# MCU.net
KiCad netlist of a schematic drawn in Altium Designer
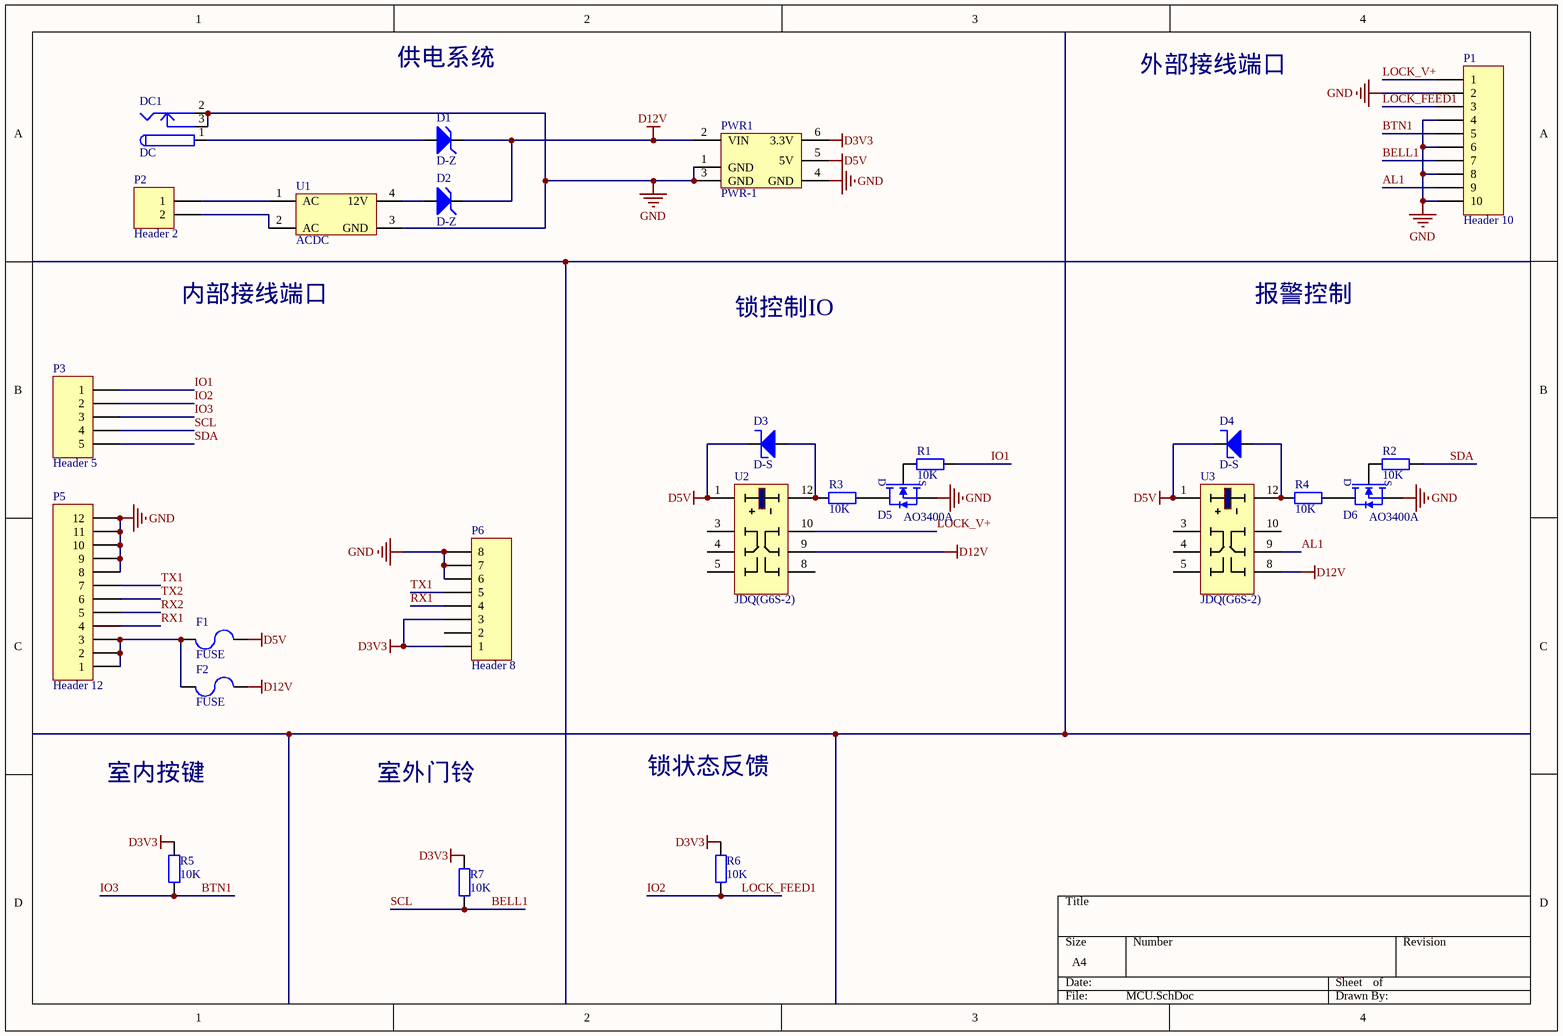
[diagram p0: MCU.SchDoc]

(export (version "E")
  (design (tool "Eeschema 10.0.6"))
  (components
    (comp (ref "D1")
      (value "D-Z")
      (footprint "DO-214AC(SMA)")
      (description "稳压二极管")
      (libsource (lib "lib_AD") (part "D-Z"))
    )
    (comp (ref "D2")
      (value "D-Z")
      (footprint "DO-214AC(SMA)")
      (description "稳压二极管")
      (libsource (lib "lib_AD") (part "D-Z"))
    )
    (comp (ref "D3")
      (value "D-S")
      (footprint "DO-214AC(SMA)")
      (description "肖特基二极管")
      (libsource (lib "lib_AD") (part "D-S"))
    )
    (comp (ref "D4")
      (value "D-S")
      (footprint "DO-214AC(SMA)")
      (description "肖特基二极管")
      (libsource (lib "lib_AD") (part "D-S"))
    )
    (comp (ref "D5")
      (value "AO3400A")
      (footprint "SOT23A")
      (description "NMOS")
      (libsource (lib "lib_AD") (part "MOS-N"))
    )
    (comp (ref "D6")
      (value "AO3400A")
      (footprint "SOT23A")
      (description "NMOS")
      (libsource (lib "lib_AD") (part "MOS-N"))
    )
    (comp (ref "DC1")
      (value "DC")
      (footprint "DC005")
      (description "圆形电源接口")
      (libsource (lib "lib_AD") (part "DC00X"))
    )
    (comp (ref "F1")
      (value "FUSE")
      (footprint "0805F")
      (description "CR-1812-050A60V")
      (libsource (lib "lib_AD") (part "FUSE"))
    )
    (comp (ref "F2")
      (value "FUSE")
      (footprint "0805F")
      (description "CR-1812-050A60V")
      (libsource (lib "lib_AD") (part "FUSE"))
    )
    (comp (ref "P1")
      (value "Header 10")
      (footprint "KF128-5.08-10")
      (description "Header, 10-Pin")
      (fields (field (name "PUBLISHER") "Altium Limited"))
      (libsource (lib "lib_AD") (part "Header 10"))
    )
    (comp (ref "P2")
      (value "Header 2")
      (footprint "KF128-5.08-2")
      (description "Header, 2-Pin")
      (fields (field (name "PUBLISHER") "Altium Limited"))
      (libsource (lib "lib_AD") (part "Header 2"))
    )
    (comp (ref "P3")
      (value "Header 5")
      (footprint "XH2.54-5")
      (description "Header, 5-Pin")
      (fields (field (name "PUBLISHER") "Altium Limited"))
      (libsource (lib "lib_AD") (part "Header 5"))
    )
    (comp (ref "P5")
      (value "Header 12")
      (footprint "FFC/SM1.0-2H10")
      (description "Header, 12-Pin")
      (fields (field (name "PUBLISHER") "Altium Limited"))
      (libsource (lib "lib_AD") (part "Header 12"))
    )
    (comp (ref "P6")
      (value "Header 8")
      (footprint "FPC/1.25T-6P")
      (description "Header, 8-Pin")
      (fields (field (name "PUBLISHER") "Altium Limited"))
      (libsource (lib "lib_AD") (part "Header 8"))
    )
    (comp (ref "PWR1") (value "PWR-1") (footprint "PWR-1") (libsource (lib "lib_AD") (part "PWR-1")))
    (comp (ref "R1")
      (value "10K")
      (footprint "0603R")
      (description "普通电阻")
      (libsource (lib "") (part "RES_1"))
    )
    (comp (ref "R2")
      (value "10K")
      (footprint "0603R")
      (description "普通电阻")
      (libsource (lib "") (part "RES_1"))
    )
    (comp (ref "R3")
      (value "10K")
      (footprint "0603R")
      (description "普通电阻")
      (libsource (lib "") (part "RES_1"))
    )
    (comp (ref "R4")
      (value "10K")
      (footprint "0603R")
      (description "普通电阻")
      (libsource (lib "") (part "RES_1"))
    )
    (comp (ref "R5")
      (value "10K")
      (footprint "0603R")
      (description "普通电阻")
      (libsource (lib "lib_AD") (part "RES"))
    )
    (comp (ref "R6")
      (value "10K")
      (footprint "0603R")
      (description "普通电阻")
      (libsource (lib "lib_AD") (part "RES"))
    )
    (comp (ref "R7")
      (value "10K")
      (footprint "0603R")
      (description "普通电阻")
      (libsource (lib "lib_AD") (part "RES"))
    )
    (comp (ref "U1") (value "ACDC") (footprint "ACDC") (libsource (lib "Misc") (part "ACDC12")))
    (comp (ref "U2")
      (value "JDQ(G6S-2)")
      (footprint "JDQ-G6S-2")
      (description "继电器（G6S-2 5VDC）")
      (libsource (lib "lib_AD") (part "JDQ(G6S-2)"))
    )
    (comp (ref "U3")
      (value "JDQ(G6S-2)")
      (footprint "JDQ-G6S-2")
      (description "继电器（G6S-2 5VDC）")
      (libsource (lib "lib_AD") (part "JDQ(G6S-2)"))
    )
  )
  (nets
    (net (code "1") (name "/AL1") (class "Default")
      (node (ref "P1") (pin "9") (pinfunction "9_9") (pintype "passive"))
      (node (ref "U3") (pin "9") (pinfunction "9_9") (pintype "passive"))
    )
    (net (code "2") (name "/BELL1") (class "Default")
      (node (ref "P1") (pin "7") (pinfunction "7_7") (pintype "passive"))
      (node (ref "P3") (pin "4") (pinfunction "4_4") (pintype "passive"))
      (node (ref "R7") (pin "1") (pinfunction "1_1") (pintype "passive"))
    )
    (net (code "3") (name "/BTN1") (class "Default")
      (node (ref "P1") (pin "5") (pinfunction "5_5") (pintype "passive"))
      (node (ref "P3") (pin "3") (pinfunction "3_3") (pintype "passive"))
      (node (ref "R5") (pin "1") (pinfunction "1_1") (pintype "passive"))
    )
    (net (code "4") (name "/IO1") (class "Default")
      (node (ref "P3") (pin "1") (pinfunction "1_1") (pintype "passive"))
      (node (ref "R1") (pin "2") (pinfunction "2_2") (pintype "passive"))
    )
    (net (code "5") (name "/IO2") (class "Default")
      (node (ref "P1") (pin "3") (pinfunction "3_3") (pintype "passive"))
      (node (ref "P3") (pin "2") (pinfunction "2_2") (pintype "passive"))
      (node (ref "R6") (pin "1") (pinfunction "1_1") (pintype "passive"))
    )
    (net (code "6") (name "/LOCK_V+") (class "Default")
      (node (ref "P1") (pin "1") (pinfunction "1_1") (pintype "passive"))
      (node (ref "U2") (pin "10") (pinfunction "10_10") (pintype "passive"))
    )
    (net (code "7") (name "/RX1") (class "Default")
      (node (ref "P5") (pin "4") (pinfunction "4_4") (pintype "passive"))
      (node (ref "P6") (pin "4") (pinfunction "4_4") (pintype "passive"))
    )
    (net (code "8") (name "/RX2") (class "Default")
      (node (ref "P5") (pin "5") (pinfunction "5_5") (pintype "passive"))
    )
    (net (code "9") (name "/SDA") (class "Default")
      (node (ref "P3") (pin "5") (pinfunction "5_5") (pintype "passive"))
      (node (ref "R2") (pin "2") (pinfunction "2_2") (pintype "passive"))
    )
    (net (code "10") (name "/TX1") (class "Default")
      (node (ref "P5") (pin "7") (pinfunction "7_7") (pintype "passive"))
      (node (ref "P6") (pin "5") (pinfunction "5_5") (pintype "passive"))
    )
    (net (code "11") (name "/TX2") (class "Default")
      (node (ref "P5") (pin "6") (pinfunction "6_6") (pintype "passive"))
    )
    (net (code "12") (name "D3V3") (class "Default")
      (node (ref "P6") (pin "1") (pinfunction "1_1") (pintype "passive"))
      (node (ref "P6") (pin "3") (pinfunction "3_3") (pintype "passive"))
      (node (ref "PWR1") (pin "6") (pinfunction "3.3V_6") (pintype "passive"))
      (node (ref "R5") (pin "2") (pinfunction "2_2") (pintype "passive"))
      (node (ref "R6") (pin "2") (pinfunction "2_2") (pintype "passive"))
      (node (ref "R7") (pin "2") (pinfunction "2_2") (pintype "passive"))
    )
    (net (code "13") (name "D5V") (class "Default")
      (node (ref "D3") (pin "K") (pinfunction "2_K") (pintype "passive"))
      (node (ref "D4") (pin "K") (pinfunction "2_K") (pintype "passive"))
      (node (ref "F1") (pin "1") (pinfunction "1_1") (pintype "passive"))
      (node (ref "PWR1") (pin "5") (pinfunction "5V_5") (pintype "passive"))
      (node (ref "U2") (pin "1") (pinfunction "1_1") (pintype "passive"))
      (node (ref "U3") (pin "1") (pinfunction "1_1") (pintype "passive"))
    )
    (net (code "14") (name "D12V") (class "Default")
      (node (ref "D1") (pin "K") (pinfunction "2_K") (pintype "passive"))
      (node (ref "D2") (pin "K") (pinfunction "2_K") (pintype "passive"))
      (node (ref "F2") (pin "1") (pinfunction "1_1") (pintype "passive"))
      (node (ref "PWR1") (pin "2") (pinfunction "VIN_2") (pintype "passive"))
      (node (ref "U2") (pin "9") (pinfunction "9_9") (pintype "passive"))
      (node (ref "U3") (pin "8") (pinfunction "8_8") (pintype "passive"))
    )
    (net (code "15") (name "GND") (class "Default")
      (node (ref "D5") (pin "2") (pinfunction "S_2") (pintype "passive"))
      (node (ref "D6") (pin "2") (pinfunction "S_2") (pintype "passive"))
      (node (ref "DC1") (pin "2") (pinfunction "2_2") (pintype "power_in"))
      (node (ref "DC1") (pin "3") (pinfunction "3_3") (pintype "power_in"))
      (node (ref "P1") (pin "10") (pinfunction "10_10") (pintype "passive"))
      (node (ref "P1") (pin "2") (pinfunction "2_2") (pintype "passive"))
      (node (ref "P1") (pin "4") (pinfunction "4_4") (pintype "passive"))
      (node (ref "P1") (pin "6") (pinfunction "6_6") (pintype "passive"))
      (node (ref "P1") (pin "8") (pinfunction "8_8") (pintype "passive"))
      (node (ref "P5") (pin "10") (pinfunction "10_10") (pintype "passive"))
      (node (ref "P5") (pin "11") (pinfunction "11_11") (pintype "passive"))
      (node (ref "P5") (pin "12") (pinfunction "12_12") (pintype "passive"))
      (node (ref "P5") (pin "8") (pinfunction "8_8") (pintype "passive"))
      (node (ref "P5") (pin "9") (pinfunction "9_9") (pintype "passive"))
      (node (ref "P6") (pin "6") (pinfunction "6_6") (pintype "passive"))
      (node (ref "P6") (pin "7") (pinfunction "7_7") (pintype "passive"))
      (node (ref "P6") (pin "8") (pinfunction "8_8") (pintype "passive"))
      (node (ref "PWR1") (pin "1") (pinfunction "GND_1") (pintype "passive"))
      (node (ref "PWR1") (pin "3") (pinfunction "GND_3") (pintype "passive"))
      (node (ref "PWR1") (pin "4") (pinfunction "GND_4") (pintype "passive"))
      (node (ref "U1") (pin "3") (pinfunction "GND_3") (pintype "passive"))
    )
    (net (code "16") (name "Net-(D1-1)") (class "Default")
      (node (ref "D1") (pin "A") (pinfunction "1_A") (pintype "passive"))
      (node (ref "DC1") (pin "1") (pinfunction "1_1") (pintype "power_in"))
    )
    (net (code "17") (name "Net-(D2-1)") (class "Default")
      (node (ref "D2") (pin "A") (pinfunction "1_A") (pintype "passive"))
      (node (ref "U1") (pin "4") (pinfunction "12V_4") (pintype "passive"))
    )
    (net (code "18") (name "Net-(D3-1)") (class "Default")
      (node (ref "D3") (pin "A") (pinfunction "1_A") (pintype "passive"))
      (node (ref "R3") (pin "1") (pinfunction "1_1") (pintype "passive"))
      (node (ref "U2") (pin "12") (pinfunction "12_12") (pintype "passive"))
    )
    (net (code "19") (name "Net-(D4-1)") (class "Default")
      (node (ref "D4") (pin "A") (pinfunction "1_A") (pintype "passive"))
      (node (ref "R4") (pin "1") (pinfunction "1_1") (pintype "passive"))
      (node (ref "U3") (pin "12") (pinfunction "12_12") (pintype "passive"))
    )
    (net (code "20") (name "Net-(D5-D)") (class "Default")
      (node (ref "D5") (pin "3") (pinfunction "D_3") (pintype "passive"))
      (node (ref "R3") (pin "2") (pinfunction "2_2") (pintype "passive"))
    )
    (net (code "21") (name "Net-(D5-G)") (class "Default")
      (node (ref "D5") (pin "1") (pinfunction "G_1") (pintype "passive"))
      (node (ref "R1") (pin "1") (pinfunction "1_1") (pintype "passive"))
    )
    (net (code "22") (name "Net-(D6-D)") (class "Default")
      (node (ref "D6") (pin "3") (pinfunction "D_3") (pintype "passive"))
      (node (ref "R4") (pin "2") (pinfunction "2_2") (pintype "passive"))
    )
    (net (code "23") (name "Net-(D6-G)") (class "Default")
      (node (ref "D6") (pin "1") (pinfunction "G_1") (pintype "passive"))
      (node (ref "R2") (pin "1") (pinfunction "1_1") (pintype "passive"))
    )
    (net (code "24") (name "Net-(F1-Pad2)") (class "Default")
      (node (ref "F1") (pin "2") (pinfunction "2_2") (pintype "passive"))
      (node (ref "F2") (pin "2") (pinfunction "2_2") (pintype "passive"))
      (node (ref "P5") (pin "1") (pinfunction "1_1") (pintype "passive"))
      (node (ref "P5") (pin "2") (pinfunction "2_2") (pintype "passive"))
      (node (ref "P5") (pin "3") (pinfunction "3_3") (pintype "passive"))
    )
    (net (code "25") (name "Net-(P2-Pad1)") (class "Default")
      (node (ref "P2") (pin "1") (pinfunction "1_1") (pintype "passive"))
      (node (ref "U1") (pin "1") (pinfunction "AC_1") (pintype "passive"))
    )
    (net (code "26") (name "Net-(P2-Pad2)") (class "Default")
      (node (ref "P2") (pin "2") (pinfunction "2_2") (pintype "passive"))
      (node (ref "U1") (pin "2") (pinfunction "AC_2") (pintype "passive"))
    )
    (net (code "27") (name "unconnected-(P6-Pad2)") (class "Default")
      (node (ref "P6") (pin "2") (pinfunction "2_2") (pintype "passive"))
    )
    (net (code "28") (name "unconnected-(U2-Pad3)") (class "Default")
      (node (ref "U2") (pin "3") (pinfunction "3_3") (pintype "passive"))
    )
    (net (code "29") (name "unconnected-(U2-Pad4)") (class "Default")
      (node (ref "U2") (pin "4") (pinfunction "4_4") (pintype "passive"))
    )
    (net (code "30") (name "unconnected-(U2-Pad5)") (class "Default")
      (node (ref "U2") (pin "5") (pinfunction "5_5") (pintype "passive"))
    )
    (net (code "31") (name "unconnected-(U2-Pad8)") (class "Default")
      (node (ref "U2") (pin "8") (pinfunction "8_8") (pintype "passive"))
    )
    (net (code "32") (name "unconnected-(U3-Pad3)") (class "Default")
      (node (ref "U3") (pin "3") (pinfunction "3_3") (pintype "passive"))
    )
    (net (code "33") (name "unconnected-(U3-Pad4)") (class "Default")
      (node (ref "U3") (pin "4") (pinfunction "4_4") (pintype "passive"))
    )
    (net (code "34") (name "unconnected-(U3-Pad5)") (class "Default")
      (node (ref "U3") (pin "5") (pinfunction "5_5") (pintype "passive"))
    )
    (net (code "35") (name "unconnected-(U3-Pad10)") (class "Default")
      (node (ref "U3") (pin "10") (pinfunction "10_10") (pintype "passive"))
    )
  )
)
